# BloodPressure.net
KiCad netlist of a schematic drawn in Altium Designer
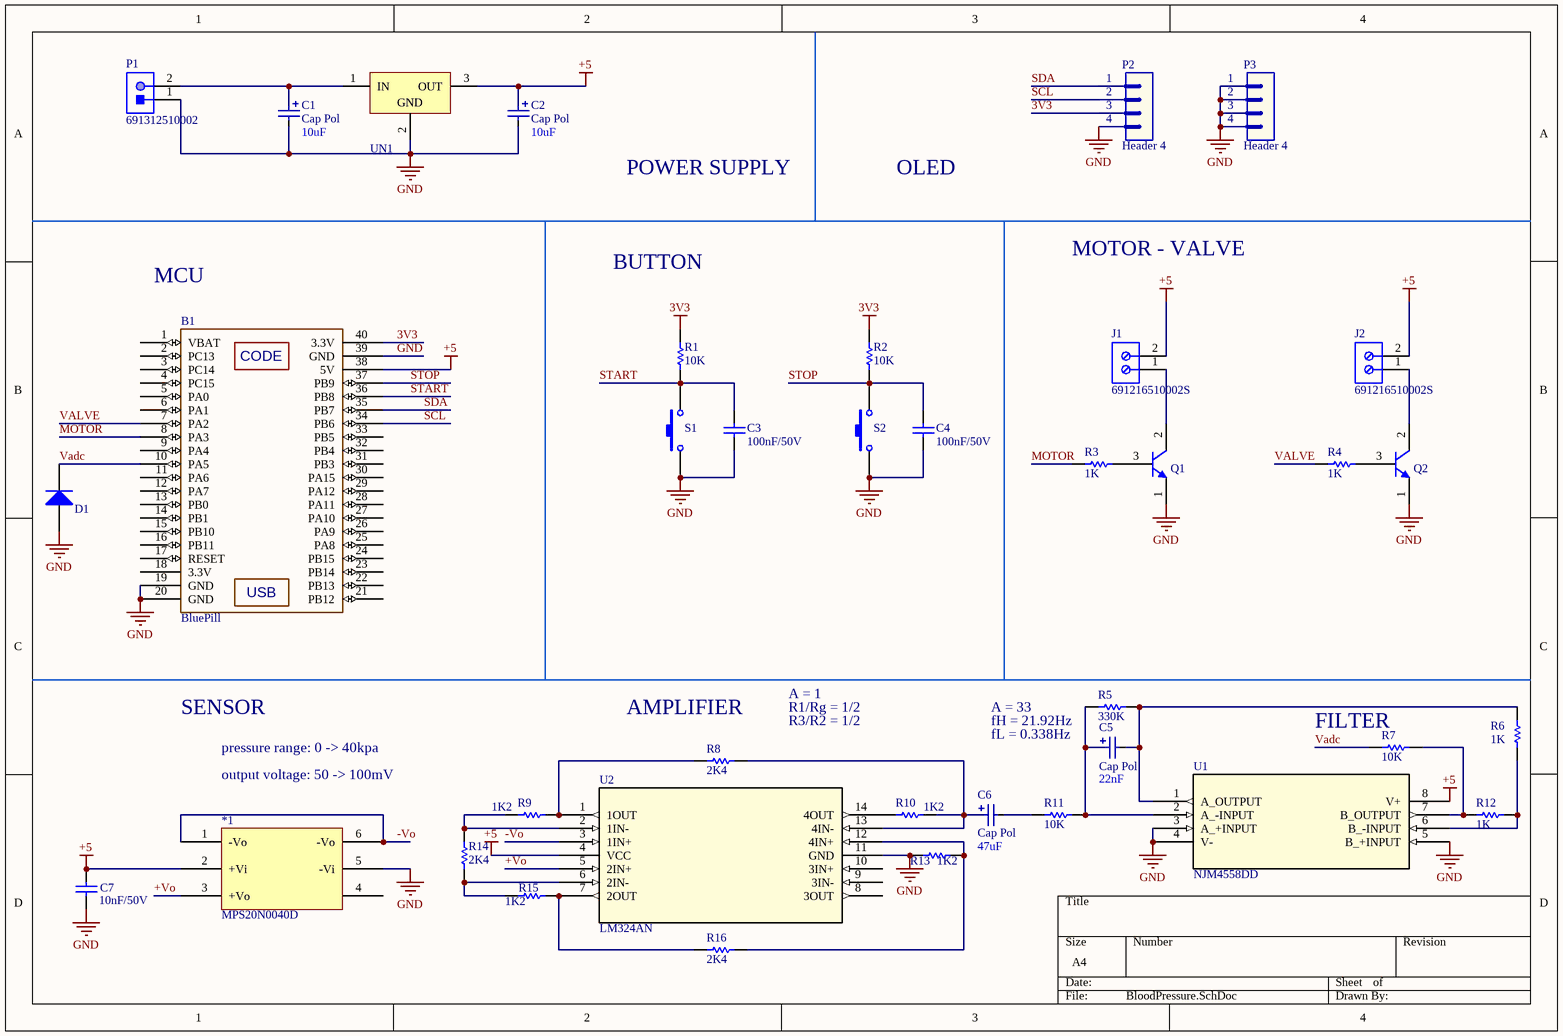
[diagram p0: BloodPressure.SchDoc]

(export (version "E")
  (design (tool "Eeschema 10.0.6"))
  (components
    (comp (ref "*1")
      (value "MPS20N0040D")
      (footprint "MPS20N0040D")
      (libsource (lib "BloodPresure") (part "MPS20N0040D"))
    )
    (comp (ref "B1")
      (value "BluePill")
      (footprint "BlUEPILL")
      (libsource (lib "dev-board") (part "BluePill"))
    )
    (comp (ref "C1")
      (value "Cap Pol")
      (footprint "CP1/2")
      (description "Polarized Capacitor (Radial)")
      (fields (field (name "ALTIUM_VALUE") "10uF"))
      (libsource (lib "capacitor-th") (part "Cap-TH-Pol"))
    )
    (comp (ref "C2")
      (value "Cap Pol")
      (footprint "CP1/2")
      (description "Polarized Capacitor (Radial)")
      (fields (field (name "ALTIUM_VALUE") "10uF"))
      (libsource (lib "capacitor-th") (part "Cap-TH-Pol"))
    )
    (comp (ref "C3")
      (value "100nF/50V")
      (footprint "CAP-SM-0805")
      (description "CAP CER 0.1UF 50V Y5V 0805")
      (fields
        (field (name "MANUFACTURER") "Samsung Electro-Mechanics")
        (field (name "MANUFACTURER PART NUMBER") "CL21F104ZBCNNNC")
      )
      (libsource (lib "capacitor-smd") (part "Cap-100nF-50V-0805"))
    )
    (comp (ref "C4")
      (value "100nF/50V")
      (footprint "CAP-SM-0805")
      (description "CAP CER 0.1UF 50V Y5V 0805")
      (fields
        (field (name "MANUFACTURER") "Samsung Electro-Mechanics")
        (field (name "MANUFACTURER PART NUMBER") "CL21F104ZBCNNNC")
      )
      (libsource (lib "capacitor-smd") (part "Cap-100nF-50V-0805"))
    )
    (comp (ref "C5")
      (value "Cap Pol")
      (footprint "CP1/2")
      (description "Polarized Capacitor (Radial)")
      (fields (field (name "ALTIUM_VALUE") "22nF"))
      (libsource (lib "capacitor-th") (part "Cap-TH-Pol"))
    )
    (comp (ref "C6")
      (value "Cap Pol")
      (footprint "CP1/2")
      (description "Polarized Capacitor (Radial)")
      (fields (field (name "ALTIUM_VALUE") "47uF"))
      (libsource (lib "capacitor-th") (part "Cap-TH-Pol"))
    )
    (comp (ref "C7")
      (value "10nF/50V")
      (footprint "CAP-SM-0805")
      (description "CAP CER 0.1UF 50V Y5V 0805")
      (fields
        (field (name "MANUFACTURER") "Samsung Electro-Mechanics")
        (field (name "MANUFACTURER PART NUMBER") "CL21F104ZBCNNNC")
      )
      (libsource (lib "capacitor-smd") (part "Cap-100nF-50V-0805"))
    )
    (comp (ref "D1")
      (value "Diode")
      (footprint "D1A")
      (description "Default Diode")
      (libsource (lib "PIF_Library") (part "Diode"))
    )
    (comp (ref "J1")
      (value "691216510002S")
      (footprint "691216510002S")
      (description "WR-TBL Serie 2165S Horizontal Entry Modular, Rising Cage Clamp, pitch 5.08mm, 2p")
      (fields (field (name "PUBLISHER") "Wurth Elektronik"))
      (libsource (lib "domino-rising-cage-clamp") (part "691216510002S"))
    )
    (comp (ref "J2")
      (value "691216510002S")
      (footprint "691216510002S")
      (description "WR-TBL Serie 2165S Horizontal Entry Modular, Rising Cage Clamp, pitch 5.08mm, 2p")
      (fields (field (name "PUBLISHER") "Wurth Elektronik"))
      (libsource (lib "domino-rising-cage-clamp") (part "691216510002S"))
    )
    (comp (ref "P1")
      (value "691312510002")
      (footprint "691312510002")
      (description "WR-TBL Serie 312 Open Horizontal PCB Header, Pluggable, pitch 5.08mm, 2p")
      (fields (field (name "PUBLISHER") "Wurth Elektronik"))
      (libsource (lib "WR-TBL_Pluggable PCB Header") (part "691312510002"))
    )
    (comp (ref "P2")
      (value "Header 4")
      (footprint "JP4")
      (description "Header, 4-Pin")
      (fields (field (name "LOCAL SUPPLIER PART NUMBER") "x") (field (name "PUBLISHER") "Altium Limited"))
      (libsource (lib "header-connector") (part "Header 4"))
    )
    (comp (ref "P3")
      (value "Header 4")
      (footprint "JP4")
      (description "Header, 4-Pin")
      (fields (field (name "LOCAL SUPPLIER PART NUMBER") "x") (field (name "PUBLISHER") "Altium Limited"))
      (libsource (lib "header-connector") (part "Header 4"))
    )
    (comp (ref "Q1")
      (value "C1815")
      (footprint "QTO-92")
      (description "NPN Bipolar Transistor")
      (libsource (lib "PIF_Library") (part "C1815"))
    )
    (comp (ref "Q2")
      (value "C1815")
      (footprint "QTO-92")
      (description "NPN Bipolar Transistor")
      (libsource (lib "PIF_Library") (part "C1815"))
    )
    (comp (ref "R1")
      (value "10K")
      (footprint "resistor-smd:RES-SM-0805")
      (description "RES 10K OHM 1% 1/4W 0805")
      (fields
        (field (name "MANUFACTURER") "Stackpole Electronics Inc")
        (field (name "MANUFACTURER PART NUMBER") "RNCP0805FTD10K0")
      )
      (libsource (lib "resistor-smd") (part "Res-10k-0805"))
    )
    (comp (ref "R2")
      (value "10K")
      (footprint "resistor-smd:RES-SM-0805")
      (description "RES 10K OHM 1% 1/4W 0805")
      (fields
        (field (name "MANUFACTURER") "Stackpole Electronics Inc")
        (field (name "MANUFACTURER PART NUMBER") "RNCP0805FTD10K0")
      )
      (libsource (lib "resistor-smd") (part "Res-10k-0805"))
    )
    (comp (ref "R3")
      (value "1K")
      (footprint "resistor-smd:RES-SM-0805")
      (description "RES 1K OHM 1% 1/4W 0805")
      (fields
        (field (name "MANUFACTURER") "Stackpole Electronics Inc")
        (field (name "MANUFACTURER PART NUMBER") "RNCP0805FTD1K00")
      )
      (libsource (lib "resistor-smd") (part "Res-1K-0805"))
    )
    (comp (ref "R4")
      (value "1K")
      (footprint "resistor-smd:RES-SM-0805")
      (description "RES 1K OHM 1% 1/4W 0805")
      (fields
        (field (name "MANUFACTURER") "Stackpole Electronics Inc")
        (field (name "MANUFACTURER PART NUMBER") "RNCP0805FTD1K00")
      )
      (libsource (lib "resistor-smd") (part "Res-1K-0805"))
    )
    (comp (ref "R5")
      (value "330K")
      (footprint "resistor-smd:RES-SM-0805")
      (description "RES 1K OHM 1% 1/4W 0805")
      (fields
        (field (name "MANUFACTURER") "Stackpole Electronics Inc")
        (field (name "MANUFACTURER PART NUMBER") "RNCP0805FTD1K00")
      )
      (libsource (lib "resistor-smd") (part "Res-1K-0805"))
    )
    (comp (ref "R6")
      (value "1K")
      (footprint "resistor-smd:RES-SM-0805")
      (description "RES 1K OHM 1% 1/4W 0805")
      (fields
        (field (name "MANUFACTURER") "Stackpole Electronics Inc")
        (field (name "MANUFACTURER PART NUMBER") "RNCP0805FTD1K00")
      )
      (libsource (lib "resistor-smd") (part "Res-1K-0805"))
    )
    (comp (ref "R7")
      (value "10K")
      (footprint "resistor-smd:RES-SM-0805")
      (description "RES 1K OHM 1% 1/4W 0805")
      (fields
        (field (name "MANUFACTURER") "Stackpole Electronics Inc")
        (field (name "MANUFACTURER PART NUMBER") "RNCP0805FTD1K00")
      )
      (libsource (lib "resistor-smd") (part "Res-1K-0805"))
    )
    (comp (ref "R8")
      (value "2K4")
      (footprint "resistor-smd:RES-SM-0805")
      (description "RES 1K OHM 1% 1/4W 0805")
      (fields
        (field (name "MANUFACTURER") "Stackpole Electronics Inc")
        (field (name "MANUFACTURER PART NUMBER") "RNCP0805FTD1K00")
      )
      (libsource (lib "resistor-smd") (part "Res-1K-0805"))
    )
    (comp (ref "R9")
      (value "1K2")
      (footprint "resistor-smd:RES-SM-0805")
      (description "RES 1K OHM 1% 1/4W 0805")
      (fields
        (field (name "MANUFACTURER") "Stackpole Electronics Inc")
        (field (name "MANUFACTURER PART NUMBER") "RNCP0805FTD1K00")
      )
      (libsource (lib "resistor-smd") (part "Res-1K-0805"))
    )
    (comp (ref "R10")
      (value "1K2")
      (footprint "resistor-smd:RES-SM-0805")
      (description "RES 1K OHM 1% 1/4W 0805")
      (fields
        (field (name "MANUFACTURER") "Stackpole Electronics Inc")
        (field (name "MANUFACTURER PART NUMBER") "RNCP0805FTD1K00")
      )
      (libsource (lib "resistor-smd") (part "Res-1K-0805"))
    )
    (comp (ref "R11")
      (value "10K")
      (footprint "resistor-smd:RES-SM-0805")
      (description "RES 1K OHM 1% 1/4W 0805")
      (fields
        (field (name "MANUFACTURER") "Stackpole Electronics Inc")
        (field (name "MANUFACTURER PART NUMBER") "RNCP0805FTD1K00")
      )
      (libsource (lib "resistor-smd") (part "Res-1K-0805"))
    )
    (comp (ref "R12")
      (value "1K")
      (footprint "resistor-smd:RES-SM-0805")
      (description "RES 1K OHM 1% 1/4W 0805")
      (fields
        (field (name "MANUFACTURER") "Stackpole Electronics Inc")
        (field (name "MANUFACTURER PART NUMBER") "RNCP0805FTD1K00")
      )
      (libsource (lib "resistor-smd") (part "Res-1K-0805"))
    )
    (comp (ref "R13")
      (value "1K2")
      (footprint "resistor-smd:RES-SM-0805")
      (description "RES 1K OHM 1% 1/4W 0805")
      (fields
        (field (name "MANUFACTURER") "Stackpole Electronics Inc")
        (field (name "MANUFACTURER PART NUMBER") "RNCP0805FTD1K00")
      )
      (libsource (lib "resistor-smd") (part "Res-1K-0805"))
    )
    (comp (ref "R14")
      (value "2K4")
      (footprint "resistor-smd:RES-SM-0805")
      (description "RES 1K OHM 1% 1/4W 0805")
      (fields
        (field (name "MANUFACTURER") "Stackpole Electronics Inc")
        (field (name "MANUFACTURER PART NUMBER") "RNCP0805FTD1K00")
      )
      (libsource (lib "resistor-smd") (part "Res-1K-0805"))
    )
    (comp (ref "R15")
      (value "1K2")
      (footprint "resistor-smd:RES-SM-0805")
      (description "RES 1K OHM 1% 1/4W 0805")
      (fields
        (field (name "MANUFACTURER") "Stackpole Electronics Inc")
        (field (name "MANUFACTURER PART NUMBER") "RNCP0805FTD1K00")
      )
      (libsource (lib "resistor-smd") (part "Res-1K-0805"))
    )
    (comp (ref "R16")
      (value "2K4")
      (footprint "resistor-smd:RES-SM-0805")
      (description "RES 1K OHM 1% 1/4W 0805")
      (fields
        (field (name "MANUFACTURER") "Stackpole Electronics Inc")
        (field (name "MANUFACTURER PART NUMBER") "RNCP0805FTD1K00")
      )
      (libsource (lib "resistor-smd") (part "Res-1K-0805"))
    )
    (comp (ref "S1")
      (value "Tact SW - 2Pin")
      (footprint "SW2")
      (description "Switch button 2 pin")
      (libsource (lib "PIF_Library") (part "Tact SW - 2Pin"))
    )
    (comp (ref "S2")
      (value "Tact SW - 2Pin")
      (footprint "SW2")
      (description "Switch button 2 pin")
      (libsource (lib "PIF_Library") (part "Tact SW - 2Pin"))
    )
    (comp (ref "U1")
      (value "NJM4558DD")
      (footprint "DIP8_NMD")
      (description "No Description Available")
      (libsource (lib "BloodPresure") (part "NJM4558DD"))
    )
    (comp (ref "U2")
      (value "LM324AN")
      (footprint "N14")
      (description "No Description Available")
      (libsource (lib "BloodPresure") (part "LM324AN"))
    )
    (comp (ref "UN1")
      (value "LM7805")
      (footprint "QTO-220")
      (description "Positive Voltage Regulator")
      (libsource (lib "PIF_Library") (part "LM7805"))
    )
  )
  (nets
    (net (code "1") (name "+5") (class "Default")
      (node (ref "*1") (pin "2") (pinfunction "+Vi_2") (pintype "passive"))
      (node (ref "B1") (pin "38") (pinfunction "5V_38") (pintype "power_in"))
      (node (ref "C2") (pin "1") (pinfunction "1_1") (pintype "passive"))
      (node (ref "C7") (pin "1") (pinfunction "1_1") (pintype "passive"))
      (node (ref "J1") (pin "2") (pinfunction "2_2") (pintype "passive"))
      (node (ref "J2") (pin "2") (pinfunction "2_2") (pintype "passive"))
      (node (ref "U1") (pin "8") (pinfunction "V+_8") (pintype "power_in"))
      (node (ref "U2") (pin "4") (pinfunction "VCC_4") (pintype "power_in"))
      (node (ref "UN1") (pin "3") (pinfunction "OUT_3") (pintype "power_in"))
    )
    (net (code "2") (name "/+Vo") (class "Default")
      (node (ref "*1") (pin "3") (pinfunction "+Vo_3") (pintype "passive"))
      (node (ref "U2") (pin "5") (pinfunction "2IN+_5") (pintype "input"))
    )
    (net (code "3") (name "/-Vo") (class "Default")
      (node (ref "*1") (pin "1") (pinfunction "-Vo_1") (pintype "passive"))
      (node (ref "*1") (pin "6") (pinfunction "-Vo_6") (pintype "passive"))
      (node (ref "U2") (pin "3") (pinfunction "1IN+_3") (pintype "input"))
    )
    (net (code "4") (name "/MOTOR") (class "Default")
      (node (ref "B1") (pin "8") (pinfunction "PA3_8") (pintype "bidirectional"))
      (node (ref "R3") (pin "1") (pinfunction "1_1") (pintype "passive"))
    )
    (net (code "5") (name "/SCL") (class "Default")
      (node (ref "B1") (pin "34") (pinfunction "PB6_34") (pintype "bidirectional"))
      (node (ref "P2") (pin "2") (pinfunction "2_2") (pintype "passive"))
    )
    (net (code "6") (name "/SDA") (class "Default")
      (node (ref "B1") (pin "35") (pinfunction "PB7_35") (pintype "bidirectional"))
      (node (ref "P2") (pin "1") (pinfunction "1_1") (pintype "passive"))
    )
    (net (code "7") (name "/START") (class "Default")
      (node (ref "B1") (pin "36") (pinfunction "PB8_36") (pintype "bidirectional"))
      (node (ref "C3") (pin "2") (pinfunction "2_2") (pintype "passive"))
      (node (ref "R1") (pin "1") (pinfunction "1_1") (pintype "passive"))
      (node (ref "S1") (pin "2") (pinfunction "2_2") (pintype "passive"))
    )
    (net (code "8") (name "/STOP") (class "Default")
      (node (ref "B1") (pin "37") (pinfunction "PB9_37") (pintype "bidirectional"))
      (node (ref "C4") (pin "2") (pinfunction "2_2") (pintype "passive"))
      (node (ref "R2") (pin "1") (pinfunction "1_1") (pintype "passive"))
      (node (ref "S2") (pin "2") (pinfunction "2_2") (pintype "passive"))
    )
    (net (code "9") (name "/VALVE") (class "Default")
      (node (ref "B1") (pin "7") (pinfunction "PA2_7") (pintype "bidirectional"))
      (node (ref "R4") (pin "1") (pinfunction "1_1") (pintype "passive"))
    )
    (net (code "10") (name "/Vadc") (class "Default")
      (node (ref "B1") (pin "10") (pinfunction "PA5_10") (pintype "bidirectional"))
      (node (ref "D1") (pin "2") (pinfunction "K_2") (pintype "passive"))
      (node (ref "R7") (pin "1") (pinfunction "1_1") (pintype "passive"))
    )
    (net (code "11") (name "3V3") (class "Default")
      (node (ref "B1") (pin "40") (pinfunction "3.3V_40") (pintype "power_in"))
      (node (ref "P2") (pin "3") (pinfunction "3_3") (pintype "passive"))
      (node (ref "R1") (pin "2") (pinfunction "2_2") (pintype "passive"))
      (node (ref "R2") (pin "2") (pinfunction "2_2") (pintype "passive"))
    )
    (net (code "12") (name "GND") (class "Default")
      (node (ref "*1") (pin "5") (pinfunction "-Vi_5") (pintype "passive"))
      (node (ref "B1") (pin "19") (pinfunction "GND_19") (pintype "power_in"))
      (node (ref "B1") (pin "20") (pinfunction "GND_20") (pintype "power_in"))
      (node (ref "B1") (pin "39") (pinfunction "GND_39") (pintype "power_in"))
      (node (ref "C1") (pin "2") (pinfunction "2_2") (pintype "passive"))
      (node (ref "C2") (pin "2") (pinfunction "2_2") (pintype "passive"))
      (node (ref "C3") (pin "1") (pinfunction "1_1") (pintype "passive"))
      (node (ref "C4") (pin "1") (pinfunction "1_1") (pintype "passive"))
      (node (ref "C7") (pin "2") (pinfunction "2_2") (pintype "passive"))
      (node (ref "D1") (pin "1") (pinfunction "A_1") (pintype "passive"))
      (node (ref "P1") (pin "1") (pinfunction "1_1") (pintype "passive"))
      (node (ref "P2") (pin "4") (pinfunction "4_4") (pintype "passive"))
      (node (ref "P3") (pin "1") (pinfunction "1_1") (pintype "passive"))
      (node (ref "P3") (pin "2") (pinfunction "2_2") (pintype "passive"))
      (node (ref "P3") (pin "3") (pinfunction "3_3") (pintype "passive"))
      (node (ref "P3") (pin "4") (pinfunction "4_4") (pintype "passive"))
      (node (ref "Q1") (pin "1") (pinfunction "E_1") (pintype "passive"))
      (node (ref "Q2") (pin "1") (pinfunction "E_1") (pintype "passive"))
      (node (ref "R13") (pin "1") (pinfunction "1_1") (pintype "passive"))
      (node (ref "S1") (pin "1") (pinfunction "1_1") (pintype "passive"))
      (node (ref "S2") (pin "1") (pinfunction "1_1") (pintype "passive"))
      (node (ref "U1") (pin "3") (pinfunction "A_+INPUT_3") (pintype "input"))
      (node (ref "U1") (pin "4") (pinfunction "V-_4") (pintype "power_in"))
      (node (ref "U1") (pin "5") (pinfunction "B_+INPUT_5") (pintype "input"))
      (node (ref "U2") (pin "11") (pinfunction "GND_11") (pintype "power_in"))
      (node (ref "UN1") (pin "2") (pinfunction "GND_2") (pintype "power_in"))
    )
    (net (code "13") (name "Net-(C6-Pad2)") (class "Default")
      (node (ref "C6") (pin "2") (pinfunction "2_2") (pintype "passive"))
      (node (ref "R11") (pin "1") (pinfunction "1_1") (pintype "passive"))
    )
    (net (code "14") (name "Net-(Q1-B)") (class "Default")
      (node (ref "Q1") (pin "3") (pinfunction "B_3") (pintype "passive"))
      (node (ref "R3") (pin "2") (pinfunction "2_2") (pintype "passive"))
    )
    (net (code "15") (name "Net-(Q1-C)") (class "Default")
      (node (ref "J1") (pin "1") (pinfunction "1_1") (pintype "passive"))
      (node (ref "Q1") (pin "2") (pinfunction "C_2") (pintype "passive"))
    )
    (net (code "16") (name "Net-(Q2-B)") (class "Default")
      (node (ref "Q2") (pin "3") (pinfunction "B_3") (pintype "passive"))
      (node (ref "R4") (pin "2") (pinfunction "2_2") (pintype "passive"))
    )
    (net (code "17") (name "Net-(Q2-C)") (class "Default")
      (node (ref "J2") (pin "1") (pinfunction "1_1") (pintype "passive"))
      (node (ref "Q2") (pin "2") (pinfunction "C_2") (pintype "passive"))
    )
    (net (code "18") (name "Net-(U1-A_-INPUT)") (class "Default")
      (node (ref "C5") (pin "1") (pinfunction "1_1") (pintype "passive"))
      (node (ref "R11") (pin "2") (pinfunction "2_2") (pintype "passive"))
      (node (ref "R5") (pin "1") (pinfunction "1_1") (pintype "passive"))
      (node (ref "U1") (pin "2") (pinfunction "A_-INPUT_2") (pintype "input"))
    )
    (net (code "19") (name "Net-(U1-A_OUTPUT)") (class "Default")
      (node (ref "C5") (pin "2") (pinfunction "2_2") (pintype "passive"))
      (node (ref "R5") (pin "2") (pinfunction "2_2") (pintype "passive"))
      (node (ref "R6") (pin "2") (pinfunction "2_2") (pintype "passive"))
      (node (ref "U1") (pin "1") (pinfunction "A_OUTPUT_1") (pintype "output"))
    )
    (net (code "20") (name "Net-(U1-B_-INPUT)") (class "Default")
      (node (ref "R12") (pin "2") (pinfunction "2_2") (pintype "passive"))
      (node (ref "R6") (pin "1") (pinfunction "1_1") (pintype "passive"))
      (node (ref "U1") (pin "6") (pinfunction "B_-INPUT_6") (pintype "input"))
    )
    (net (code "21") (name "Net-(U1-B_OUTPUT)") (class "Default")
      (node (ref "R12") (pin "1") (pinfunction "1_1") (pintype "passive"))
      (node (ref "R7") (pin "2") (pinfunction "2_2") (pintype "passive"))
      (node (ref "U1") (pin "7") (pinfunction "B_OUTPUT_7") (pintype "output"))
    )
    (net (code "22") (name "Net-(U2-1IN-)") (class "Default")
      (node (ref "R14") (pin "2") (pinfunction "2_2") (pintype "passive"))
      (node (ref "R9") (pin "1") (pinfunction "1_1") (pintype "passive"))
      (node (ref "U2") (pin "2") (pinfunction "1IN-_2") (pintype "input"))
    )
    (net (code "23") (name "Net-(U2-1OUT)") (class "Default")
      (node (ref "R8") (pin "1") (pinfunction "1_1") (pintype "passive"))
      (node (ref "R9") (pin "2") (pinfunction "2_2") (pintype "passive"))
      (node (ref "U2") (pin "1") (pinfunction "1OUT_1") (pintype "output"))
    )
    (net (code "24") (name "Net-(U2-2IN-)") (class "Default")
      (node (ref "R14") (pin "1") (pinfunction "1_1") (pintype "passive"))
      (node (ref "R15") (pin "1") (pinfunction "1_1") (pintype "passive"))
      (node (ref "U2") (pin "6") (pinfunction "2IN-_6") (pintype "input"))
    )
    (net (code "25") (name "Net-(U2-2OUT)") (class "Default")
      (node (ref "R15") (pin "2") (pinfunction "2_2") (pintype "passive"))
      (node (ref "R16") (pin "1") (pinfunction "1_1") (pintype "passive"))
      (node (ref "U2") (pin "7") (pinfunction "2OUT_7") (pintype "output"))
    )
    (net (code "26") (name "Net-(U2-4IN+)") (class "Default")
      (node (ref "R13") (pin "2") (pinfunction "2_2") (pintype "passive"))
      (node (ref "R16") (pin "2") (pinfunction "2_2") (pintype "passive"))
      (node (ref "U2") (pin "12") (pinfunction "4IN+_12") (pintype "input"))
    )
    (net (code "27") (name "Net-(U2-4IN-)") (class "Default")
      (node (ref "C6") (pin "1") (pinfunction "1_1") (pintype "passive"))
      (node (ref "R10") (pin "2") (pinfunction "2_2") (pintype "passive"))
      (node (ref "R8") (pin "2") (pinfunction "2_2") (pintype "passive"))
      (node (ref "U2") (pin "13") (pinfunction "4IN-_13") (pintype "input"))
    )
    (net (code "28") (name "Net-(U2-4OUT)") (class "Default")
      (node (ref "R10") (pin "1") (pinfunction "1_1") (pintype "passive"))
      (node (ref "U2") (pin "14") (pinfunction "4OUT_14") (pintype "output"))
    )
    (net (code "29") (name "Net-(UN1-IN)") (class "Default")
      (node (ref "C1") (pin "1") (pinfunction "1_1") (pintype "passive"))
      (node (ref "P1") (pin "2") (pinfunction "2_2") (pintype "passive"))
      (node (ref "UN1") (pin "1") (pinfunction "IN_1") (pintype "power_in"))
    )
    (net (code "30") (name "unconnected-(*1-Pad4)") (class "Default")
      (node (ref "*1") (pin "4") (pintype "passive"))
    )
    (net (code "31") (name "unconnected-(B1-3.3V-Pad18)") (class "Default")
      (node (ref "B1") (pin "18") (pinfunction "3.3V_18") (pintype "power_in"))
    )
    (net (code "32") (name "unconnected-(B1-PA0-Pad5)") (class "Default")
      (node (ref "B1") (pin "5") (pinfunction "PA0_5") (pintype "bidirectional"))
    )
    (net (code "33") (name "unconnected-(B1-PA1-Pad6)") (class "Default")
      (node (ref "B1") (pin "6") (pinfunction "PA1_6") (pintype "bidirectional"))
    )
    (net (code "34") (name "unconnected-(B1-PA4-Pad9)") (class "Default")
      (node (ref "B1") (pin "9") (pinfunction "PA4_9") (pintype "bidirectional"))
    )
    (net (code "35") (name "unconnected-(B1-PA6-Pad11)") (class "Default")
      (node (ref "B1") (pin "11") (pinfunction "PA6_11") (pintype "bidirectional"))
    )
    (net (code "36") (name "unconnected-(B1-PA7-Pad12)") (class "Default")
      (node (ref "B1") (pin "12") (pinfunction "PA7_12") (pintype "bidirectional"))
    )
    (net (code "37") (name "unconnected-(B1-PA8-Pad25)") (class "Default")
      (node (ref "B1") (pin "25") (pinfunction "PA8_25") (pintype "bidirectional"))
    )
    (net (code "38") (name "unconnected-(B1-PA9-Pad26)") (class "Default")
      (node (ref "B1") (pin "26") (pinfunction "PA9_26") (pintype "bidirectional"))
    )
    (net (code "39") (name "unconnected-(B1-PA10-Pad27)") (class "Default")
      (node (ref "B1") (pin "27") (pinfunction "PA10_27") (pintype "bidirectional"))
    )
    (net (code "40") (name "unconnected-(B1-PA11-Pad28)") (class "Default")
      (node (ref "B1") (pin "28") (pinfunction "PA11_28") (pintype "bidirectional"))
    )
    (net (code "41") (name "unconnected-(B1-PA12-Pad29)") (class "Default")
      (node (ref "B1") (pin "29") (pinfunction "PA12_29") (pintype "bidirectional"))
    )
    (net (code "42") (name "unconnected-(B1-PA15-Pad30)") (class "Default")
      (node (ref "B1") (pin "30") (pinfunction "PA15_30") (pintype "bidirectional"))
    )
    (net (code "43") (name "unconnected-(B1-PB0-Pad13)") (class "Default")
      (node (ref "B1") (pin "13") (pinfunction "PB0_13") (pintype "bidirectional"))
    )
    (net (code "44") (name "unconnected-(B1-PB1-Pad14)") (class "Default")
      (node (ref "B1") (pin "14") (pinfunction "PB1_14") (pintype "bidirectional"))
    )
    (net (code "45") (name "unconnected-(B1-PB3-Pad31)") (class "Default")
      (node (ref "B1") (pin "31") (pinfunction "PB3_31") (pintype "bidirectional"))
    )
    (net (code "46") (name "unconnected-(B1-PB4-Pad32)") (class "Default")
      (node (ref "B1") (pin "32") (pinfunction "PB4_32") (pintype "bidirectional"))
    )
    (net (code "47") (name "unconnected-(B1-PB5-Pad33)") (class "Default")
      (node (ref "B1") (pin "33") (pinfunction "PB5_33") (pintype "bidirectional"))
    )
    (net (code "48") (name "unconnected-(B1-PB10-Pad15)") (class "Default")
      (node (ref "B1") (pin "15") (pinfunction "PB10_15") (pintype "bidirectional"))
    )
    (net (code "49") (name "unconnected-(B1-PB11-Pad16)") (class "Default")
      (node (ref "B1") (pin "16") (pinfunction "PB11_16") (pintype "bidirectional"))
    )
    (net (code "50") (name "unconnected-(B1-PB12-Pad21)") (class "Default")
      (node (ref "B1") (pin "21") (pinfunction "PB12_21") (pintype "bidirectional"))
    )
    (net (code "51") (name "unconnected-(B1-PB13-Pad22)") (class "Default")
      (node (ref "B1") (pin "22") (pinfunction "PB13_22") (pintype "bidirectional"))
    )
    (net (code "52") (name "unconnected-(B1-PB14-Pad23)") (class "Default")
      (node (ref "B1") (pin "23") (pinfunction "PB14_23") (pintype "bidirectional"))
    )
    (net (code "53") (name "unconnected-(B1-PB15-Pad24)") (class "Default")
      (node (ref "B1") (pin "24") (pinfunction "PB15_24") (pintype "bidirectional"))
    )
    (net (code "54") (name "unconnected-(B1-PC13-Pad2)") (class "Default")
      (node (ref "B1") (pin "2") (pinfunction "PC13_2") (pintype "bidirectional"))
    )
    (net (code "55") (name "unconnected-(B1-PC14-Pad3)") (class "Default")
      (node (ref "B1") (pin "3") (pinfunction "PC14_3") (pintype "bidirectional"))
    )
    (net (code "56") (name "unconnected-(B1-PC15-Pad4)") (class "Default")
      (node (ref "B1") (pin "4") (pinfunction "PC15_4") (pintype "bidirectional"))
    )
    (net (code "57") (name "unconnected-(B1-RESET-Pad17)") (class "Default")
      (node (ref "B1") (pin "17") (pinfunction "RESET_17") (pintype "bidirectional"))
    )
    (net (code "58") (name "unconnected-(B1-VBAT-Pad1)") (class "Default")
      (node (ref "B1") (pin "1") (pinfunction "VBAT_1") (pintype "bidirectional"))
    )
    (net (code "59") (name "unconnected-(U2-3IN+-Pad10)") (class "Default")
      (node (ref "U2") (pin "10") (pinfunction "3IN+_10") (pintype "input"))
    )
    (net (code "60") (name "unconnected-(U2-3IN--Pad9)") (class "Default")
      (node (ref "U2") (pin "9") (pinfunction "3IN-_9") (pintype "input"))
    )
    (net (code "61") (name "unconnected-(U2-3OUT-Pad8)") (class "Default")
      (node (ref "U2") (pin "8") (pinfunction "3OUT_8") (pintype "output"))
    )
  )
)
